# Lightsaber.net
KiCad netlist of a schematic drawn in EAGLE
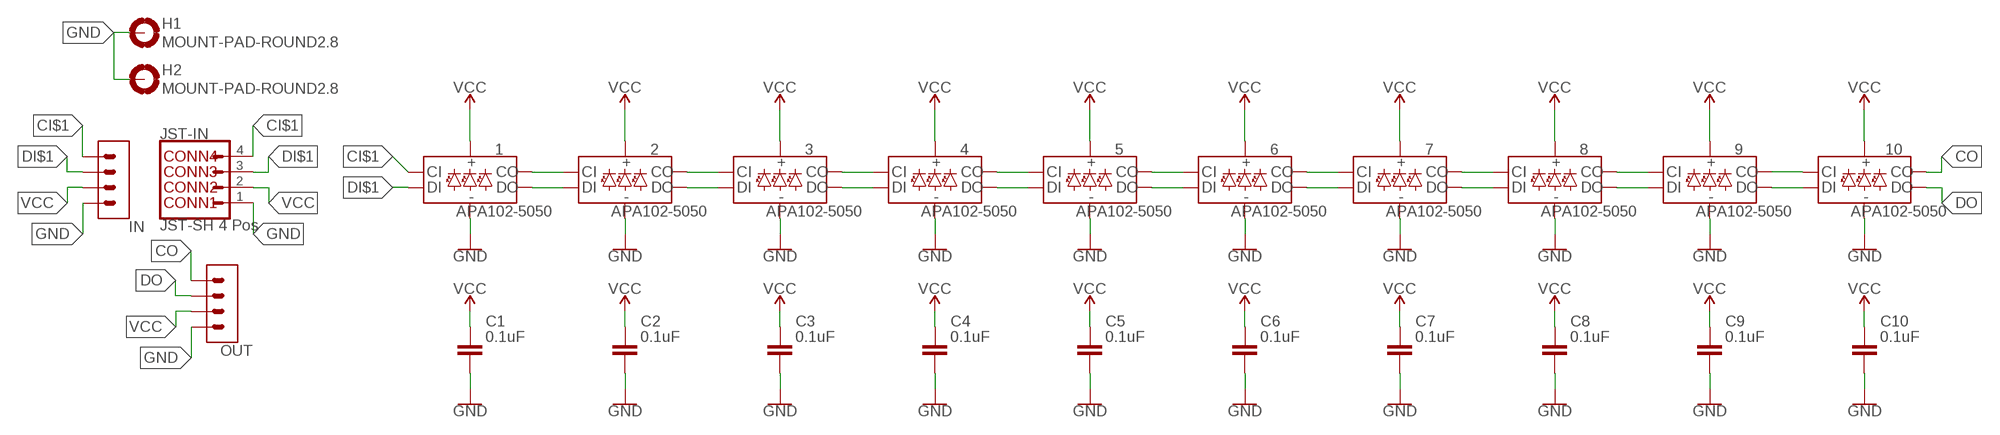
[diagram p0: schematic, sheet 1]

(export (version "E")
  (design (tool "Eeschema 10.0.6"))
  (components
    (comp (ref "1")
      (value "APA102-5050")
      (footprint "eagle-import:APA102-5050")
      (libsource (lib "eagle-import") (part "APA102-5050"))
    )
    (comp (ref "2")
      (value "APA102-5050")
      (footprint "eagle-import:APA102-5050")
      (libsource (lib "eagle-import") (part "APA102-5050"))
    )
    (comp (ref "3")
      (value "APA102-5050")
      (footprint "eagle-import:APA102-5050")
      (libsource (lib "eagle-import") (part "APA102-5050"))
    )
    (comp (ref "4")
      (value "APA102-5050")
      (footprint "eagle-import:APA102-5050")
      (libsource (lib "eagle-import") (part "APA102-5050"))
    )
    (comp (ref "5")
      (value "APA102-5050")
      (footprint "eagle-import:APA102-5050")
      (libsource (lib "eagle-import") (part "APA102-5050"))
    )
    (comp (ref "6")
      (value "APA102-5050")
      (footprint "eagle-import:APA102-5050")
      (libsource (lib "eagle-import") (part "APA102-5050"))
    )
    (comp (ref "7")
      (value "APA102-5050")
      (footprint "eagle-import:APA102-5050")
      (libsource (lib "eagle-import") (part "APA102-5050"))
    )
    (comp (ref "8")
      (value "APA102-5050")
      (footprint "eagle-import:APA102-5050")
      (libsource (lib "eagle-import") (part "APA102-5050"))
    )
    (comp (ref "9")
      (value "APA102-5050")
      (footprint "eagle-import:APA102-5050")
      (libsource (lib "eagle-import") (part "APA102-5050"))
    )
    (comp (ref "10")
      (value "APA102-5050")
      (footprint "eagle-import:APA102-5050")
      (libsource (lib "eagle-import") (part "APA102-5050"))
    )
    (comp (ref "C1")
      (value "0.1uF")
      (footprint "eagle-import:CAPC2012X110")
      (libsource (lib "eagle-import") (part "CCHIP-0805(2012-METRIC)_"))
    )
    (comp (ref "C2")
      (value "0.1uF")
      (footprint "eagle-import:CAPC2012X110")
      (libsource (lib "eagle-import") (part "CCHIP-0805(2012-METRIC)_"))
    )
    (comp (ref "C3")
      (value "0.1uF")
      (footprint "eagle-import:CAPC2012X110")
      (libsource (lib "eagle-import") (part "CCHIP-0805(2012-METRIC)_"))
    )
    (comp (ref "C4")
      (value "0.1uF")
      (footprint "eagle-import:CAPC2012X110")
      (libsource (lib "eagle-import") (part "CCHIP-0805(2012-METRIC)_"))
    )
    (comp (ref "C5")
      (value "0.1uF")
      (footprint "eagle-import:CAPC2012X110")
      (libsource (lib "eagle-import") (part "CCHIP-0805(2012-METRIC)_"))
    )
    (comp (ref "C6")
      (value "0.1uF")
      (footprint "eagle-import:CAPC2012X110")
      (libsource (lib "eagle-import") (part "CCHIP-0805(2012-METRIC)_"))
    )
    (comp (ref "C7")
      (value "0.1uF")
      (footprint "eagle-import:CAPC2012X110")
      (libsource (lib "eagle-import") (part "CCHIP-0805(2012-METRIC)_"))
    )
    (comp (ref "C8")
      (value "0.1uF")
      (footprint "eagle-import:CAPC2012X110")
      (libsource (lib "eagle-import") (part "CCHIP-0805(2012-METRIC)_"))
    )
    (comp (ref "C9")
      (value "0.1uF")
      (footprint "eagle-import:CAPC2012X110")
      (libsource (lib "eagle-import") (part "CCHIP-0805(2012-METRIC)_"))
    )
    (comp (ref "C10")
      (value "0.1uF")
      (footprint "eagle-import:CAPC2012X110")
      (libsource (lib "eagle-import") (part "CCHIP-0805(2012-METRIC)_"))
    )
    (comp (ref "H1")
      (value "MOUNT-PAD-ROUND2.8")
      (footprint "eagle-import:2,8-PAD")
      (libsource (lib "eagle-import") (part "MOUNT-PAD-ROUND2.8"))
    )
    (comp (ref "H2")
      (value "MOUNT-PAD-ROUND2.8")
      (footprint "eagle-import:2,8-PAD")
      (libsource (lib "eagle-import") (part "MOUNT-PAD-ROUND2.8"))
    )
    (comp (ref "IN")
      (value "62000411121")
      (footprint "eagle-import:62000411121")
      (fields (field (name "MANUFACTURER") "Würth Elektronik ") (field (name "CREATED_BY") "PCBLayout.com"))
      (libsource (lib "eagle-import") (part "62000411121"))
    )
    (comp (ref "JST-IN")
      (value "JST-SH 4 Pos")
      (footprint "eagle-import:JST04_1MM_VERT")
      (libsource (lib "eagle-import") (part "JST-4-SH"))
    )
    (comp (ref "OUT")
      (value "62000411121")
      (footprint "eagle-import:62000411121")
      (fields (field (name "MANUFACTURER") "Würth Elektronik ") (field (name "CREATED_BY") "PCBLayout.com"))
      (libsource (lib "eagle-import") (part "62000411121"))
    )
  )
  (nets
    (net (code "1") (name "CI$1") (class "Default")
      (node (ref "1") (pin "P2") (pinfunction "CI_P2") (pintype "bidirectional"))
      (node (ref "IN") (pin "4") (pinfunction "4_4") (pintype "passive"))
      (node (ref "JST-IN") (pin "4") (pinfunction "4_4") (pintype "passive"))
    )
    (net (code "2") (name "CO") (class "Default")
      (node (ref "10") (pin "P5") (pinfunction "CO_P5") (pintype "bidirectional"))
      (node (ref "OUT") (pin "4") (pinfunction "4_4") (pintype "passive"))
    )
    (net (code "3") (name "DI$1") (class "Default")
      (node (ref "1") (pin "P1") (pinfunction "DI_P1") (pintype "bidirectional"))
      (node (ref "IN") (pin "3") (pinfunction "3_3") (pintype "passive"))
      (node (ref "JST-IN") (pin "3") (pinfunction "3_3") (pintype "passive"))
    )
    (net (code "4") (name "DO") (class "Default")
      (node (ref "10") (pin "P6") (pinfunction "DO_P6") (pintype "bidirectional"))
      (node (ref "OUT") (pin "3") (pinfunction "3_3") (pintype "passive"))
    )
    (net (code "5") (name "GND") (class "Default")
      (node (ref "1") (pin "P3") (pinfunction "GND_P3") (pintype "bidirectional"))
      (node (ref "10") (pin "P3") (pinfunction "GND_P3") (pintype "bidirectional"))
      (node (ref "2") (pin "P3") (pinfunction "GND_P3") (pintype "bidirectional"))
      (node (ref "3") (pin "P3") (pinfunction "GND_P3") (pintype "bidirectional"))
      (node (ref "4") (pin "P3") (pinfunction "GND_P3") (pintype "bidirectional"))
      (node (ref "5") (pin "P3") (pinfunction "GND_P3") (pintype "bidirectional"))
      (node (ref "6") (pin "P3") (pinfunction "GND_P3") (pintype "bidirectional"))
      (node (ref "7") (pin "P3") (pinfunction "GND_P3") (pintype "bidirectional"))
      (node (ref "8") (pin "P3") (pinfunction "GND_P3") (pintype "bidirectional"))
      (node (ref "9") (pin "P3") (pinfunction "GND_P3") (pintype "bidirectional"))
      (node (ref "C1") (pin "2") (pinfunction "2_2") (pintype "passive"))
      (node (ref "C10") (pin "2") (pinfunction "2_2") (pintype "passive"))
      (node (ref "C2") (pin "2") (pinfunction "2_2") (pintype "passive"))
      (node (ref "C3") (pin "2") (pinfunction "2_2") (pintype "passive"))
      (node (ref "C4") (pin "2") (pinfunction "2_2") (pintype "passive"))
      (node (ref "C5") (pin "2") (pinfunction "2_2") (pintype "passive"))
      (node (ref "C6") (pin "2") (pinfunction "2_2") (pintype "passive"))
      (node (ref "C7") (pin "2") (pinfunction "2_2") (pintype "passive"))
      (node (ref "C8") (pin "2") (pinfunction "2_2") (pintype "passive"))
      (node (ref "C9") (pin "2") (pinfunction "2_2") (pintype "passive"))
      (node (ref "H1") (pin "B2,8") (pinfunction "MOUNT_B2,8") (pintype "passive"))
      (node (ref "H2") (pin "B2,8") (pinfunction "MOUNT_B2,8") (pintype "passive"))
      (node (ref "IN") (pin "1") (pinfunction "1_1") (pintype "passive"))
      (node (ref "JST-IN") (pin "1") (pinfunction "1_1") (pintype "power_in"))
      (node (ref "OUT") (pin "1") (pinfunction "1_1") (pintype "passive"))
    )
    (net (code "6") (name "Net-(1-CO)") (class "Default")
      (node (ref "1") (pin "P5") (pinfunction "CO_P5") (pintype "bidirectional"))
      (node (ref "2") (pin "P2") (pinfunction "CI_P2") (pintype "bidirectional"))
    )
    (net (code "7") (name "Net-(1-DO)") (class "Default")
      (node (ref "1") (pin "P6") (pinfunction "DO_P6") (pintype "bidirectional"))
      (node (ref "2") (pin "P1") (pinfunction "DI_P1") (pintype "bidirectional"))
    )
    (net (code "8") (name "Net-(2-CO)") (class "Default")
      (node (ref "2") (pin "P5") (pinfunction "CO_P5") (pintype "bidirectional"))
      (node (ref "3") (pin "P2") (pinfunction "CI_P2") (pintype "bidirectional"))
    )
    (net (code "9") (name "Net-(2-DO)") (class "Default")
      (node (ref "2") (pin "P6") (pinfunction "DO_P6") (pintype "bidirectional"))
      (node (ref "3") (pin "P1") (pinfunction "DI_P1") (pintype "bidirectional"))
    )
    (net (code "10") (name "Net-(3-CO)") (class "Default")
      (node (ref "3") (pin "P5") (pinfunction "CO_P5") (pintype "bidirectional"))
      (node (ref "4") (pin "P2") (pinfunction "CI_P2") (pintype "bidirectional"))
    )
    (net (code "11") (name "Net-(3-DO)") (class "Default")
      (node (ref "3") (pin "P6") (pinfunction "DO_P6") (pintype "bidirectional"))
      (node (ref "4") (pin "P1") (pinfunction "DI_P1") (pintype "bidirectional"))
    )
    (net (code "12") (name "Net-(4-CO)") (class "Default")
      (node (ref "4") (pin "P5") (pinfunction "CO_P5") (pintype "bidirectional"))
      (node (ref "5") (pin "P2") (pinfunction "CI_P2") (pintype "bidirectional"))
    )
    (net (code "13") (name "Net-(4-DO)") (class "Default")
      (node (ref "4") (pin "P6") (pinfunction "DO_P6") (pintype "bidirectional"))
      (node (ref "5") (pin "P1") (pinfunction "DI_P1") (pintype "bidirectional"))
    )
    (net (code "14") (name "Net-(5-CO)") (class "Default")
      (node (ref "5") (pin "P5") (pinfunction "CO_P5") (pintype "bidirectional"))
      (node (ref "6") (pin "P2") (pinfunction "CI_P2") (pintype "bidirectional"))
    )
    (net (code "15") (name "Net-(5-DO)") (class "Default")
      (node (ref "5") (pin "P6") (pinfunction "DO_P6") (pintype "bidirectional"))
      (node (ref "6") (pin "P1") (pinfunction "DI_P1") (pintype "bidirectional"))
    )
    (net (code "16") (name "Net-(6-CO)") (class "Default")
      (node (ref "6") (pin "P5") (pinfunction "CO_P5") (pintype "bidirectional"))
      (node (ref "7") (pin "P2") (pinfunction "CI_P2") (pintype "bidirectional"))
    )
    (net (code "17") (name "Net-(6-DO)") (class "Default")
      (node (ref "6") (pin "P6") (pinfunction "DO_P6") (pintype "bidirectional"))
      (node (ref "7") (pin "P1") (pinfunction "DI_P1") (pintype "bidirectional"))
    )
    (net (code "18") (name "Net-(7-CO)") (class "Default")
      (node (ref "7") (pin "P5") (pinfunction "CO_P5") (pintype "bidirectional"))
      (node (ref "8") (pin "P2") (pinfunction "CI_P2") (pintype "bidirectional"))
    )
    (net (code "19") (name "Net-(7-DO)") (class "Default")
      (node (ref "7") (pin "P6") (pinfunction "DO_P6") (pintype "bidirectional"))
      (node (ref "8") (pin "P1") (pinfunction "DI_P1") (pintype "bidirectional"))
    )
    (net (code "20") (name "Net-(8-CO)") (class "Default")
      (node (ref "8") (pin "P5") (pinfunction "CO_P5") (pintype "bidirectional"))
      (node (ref "9") (pin "P2") (pinfunction "CI_P2") (pintype "bidirectional"))
    )
    (net (code "21") (name "Net-(8-DO)") (class "Default")
      (node (ref "8") (pin "P6") (pinfunction "DO_P6") (pintype "bidirectional"))
      (node (ref "9") (pin "P1") (pinfunction "DI_P1") (pintype "bidirectional"))
    )
    (net (code "22") (name "Net-(10-CI)") (class "Default")
      (node (ref "10") (pin "P2") (pinfunction "CI_P2") (pintype "bidirectional"))
      (node (ref "9") (pin "P5") (pinfunction "CO_P5") (pintype "bidirectional"))
    )
    (net (code "23") (name "Net-(10-DI)") (class "Default")
      (node (ref "10") (pin "P1") (pinfunction "DI_P1") (pintype "bidirectional"))
      (node (ref "9") (pin "P6") (pinfunction "DO_P6") (pintype "bidirectional"))
    )
    (net (code "24") (name "VCC") (class "Default")
      (node (ref "1") (pin "P4") (pinfunction "VCC_P4") (pintype "bidirectional"))
      (node (ref "10") (pin "P4") (pinfunction "VCC_P4") (pintype "bidirectional"))
      (node (ref "2") (pin "P4") (pinfunction "VCC_P4") (pintype "bidirectional"))
      (node (ref "3") (pin "P4") (pinfunction "VCC_P4") (pintype "bidirectional"))
      (node (ref "4") (pin "P4") (pinfunction "VCC_P4") (pintype "bidirectional"))
      (node (ref "5") (pin "P4") (pinfunction "VCC_P4") (pintype "bidirectional"))
      (node (ref "6") (pin "P4") (pinfunction "VCC_P4") (pintype "bidirectional"))
      (node (ref "7") (pin "P4") (pinfunction "VCC_P4") (pintype "bidirectional"))
      (node (ref "8") (pin "P4") (pinfunction "VCC_P4") (pintype "bidirectional"))
      (node (ref "9") (pin "P4") (pinfunction "VCC_P4") (pintype "bidirectional"))
      (node (ref "C1") (pin "1") (pinfunction "1_1") (pintype "passive"))
      (node (ref "C10") (pin "1") (pinfunction "1_1") (pintype "passive"))
      (node (ref "C2") (pin "1") (pinfunction "1_1") (pintype "passive"))
      (node (ref "C3") (pin "1") (pinfunction "1_1") (pintype "passive"))
      (node (ref "C4") (pin "1") (pinfunction "1_1") (pintype "passive"))
      (node (ref "C5") (pin "1") (pinfunction "1_1") (pintype "passive"))
      (node (ref "C6") (pin "1") (pinfunction "1_1") (pintype "passive"))
      (node (ref "C7") (pin "1") (pinfunction "1_1") (pintype "passive"))
      (node (ref "C8") (pin "1") (pinfunction "1_1") (pintype "passive"))
      (node (ref "C9") (pin "1") (pinfunction "1_1") (pintype "passive"))
      (node (ref "IN") (pin "2") (pinfunction "2_2") (pintype "passive"))
      (node (ref "JST-IN") (pin "2") (pinfunction "2_2") (pintype "power_in"))
      (node (ref "OUT") (pin "2") (pinfunction "2_2") (pintype "passive"))
    )
  )
)
